# sensorModel.net
KiCad netlist of a schematic drawn in Altium Designer
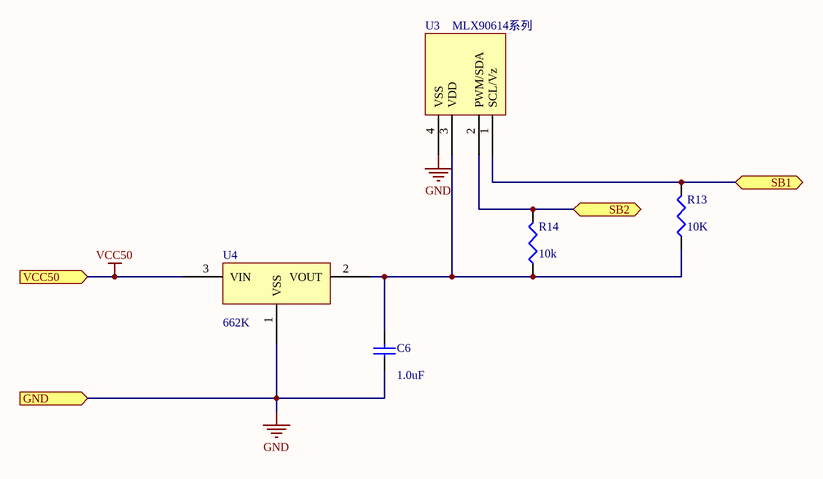
[diagram p0: sensorModel.SchDoc]

(export (version "E")
  (design (tool "Eeschema 10.0.6"))
  (components
    (comp (ref "C6")
      (value "1.0uF")
      (footprint "cap-0805")
      (description "Capacitor")
      (fields (field (name "PUBLISHER") "Altium Limited"))
      (libsource (lib "Miscellaneous Devices") (part "Cap"))
    )
    (comp (ref "R13")
      (value "10K")
      (footprint "RES-1206")
      (description "Resistor")
      (fields (field (name "PUBLISHER") "Altium Limited"))
      (libsource (lib "Miscellaneous Devices") (part "Res3"))
    )
    (comp (ref "R14")
      (value "10k")
      (footprint "RES-1206")
      (description "Resistor")
      (fields (field (name "PUBLISHER") "Altium Limited"))
      (libsource (lib "Miscellaneous Devices") (part "Res3"))
    )
    (comp (ref "U3")
      (value "MLX90614系列")
      (footprint "MLX90614XCX")
      (description "迈来芯高精度红外测温传感器")
      (libsource (lib "PqxSchlib") (part "MLX90614系列"))
    )
    (comp (ref "U4") (value "662K") (footprint "SOT23-3_L") (libsource (lib "PqxSchlib") (part "662K")))
  )
  (nets
    (net (code "1") (name "/SB1") (class "Default")
      (node (ref "R13") (pin "2") (pinfunction "2_2") (pintype "passive"))
      (node (ref "U3") (pin "1") (pinfunction "SCL/Vz_1") (pintype "passive"))
    )
    (net (code "2") (name "/SB2") (class "Default")
      (node (ref "R14") (pin "2") (pinfunction "2_2") (pintype "passive"))
      (node (ref "U3") (pin "2") (pinfunction "PWM/SDA_2") (pintype "passive"))
    )
    (net (code "3") (name "GND") (class "Default")
      (node (ref "C6") (pin "1") (pinfunction "1_1") (pintype "passive"))
      (node (ref "U3") (pin "4") (pinfunction "VSS_4") (pintype "passive"))
      (node (ref "U4") (pin "1") (pinfunction "VSS_1") (pintype "passive"))
    )
    (net (code "4") (name "Net-(U3-VDD)") (class "Default")
      (node (ref "C6") (pin "2") (pinfunction "2_2") (pintype "passive"))
      (node (ref "R13") (pin "1") (pinfunction "1_1") (pintype "passive"))
      (node (ref "R14") (pin "1") (pinfunction "1_1") (pintype "passive"))
      (node (ref "U3") (pin "3") (pinfunction "VDD_3") (pintype "passive"))
      (node (ref "U4") (pin "2") (pinfunction "VOUT_2") (pintype "passive"))
    )
    (net (code "5") (name "VCC50") (class "Default")
      (node (ref "U4") (pin "3") (pinfunction "VIN_3") (pintype "passive"))
    )
  )
)
